# ProbadorDeCables_Conexiones_A.net
KiCad netlist of a schematic drawn in Altium Designer
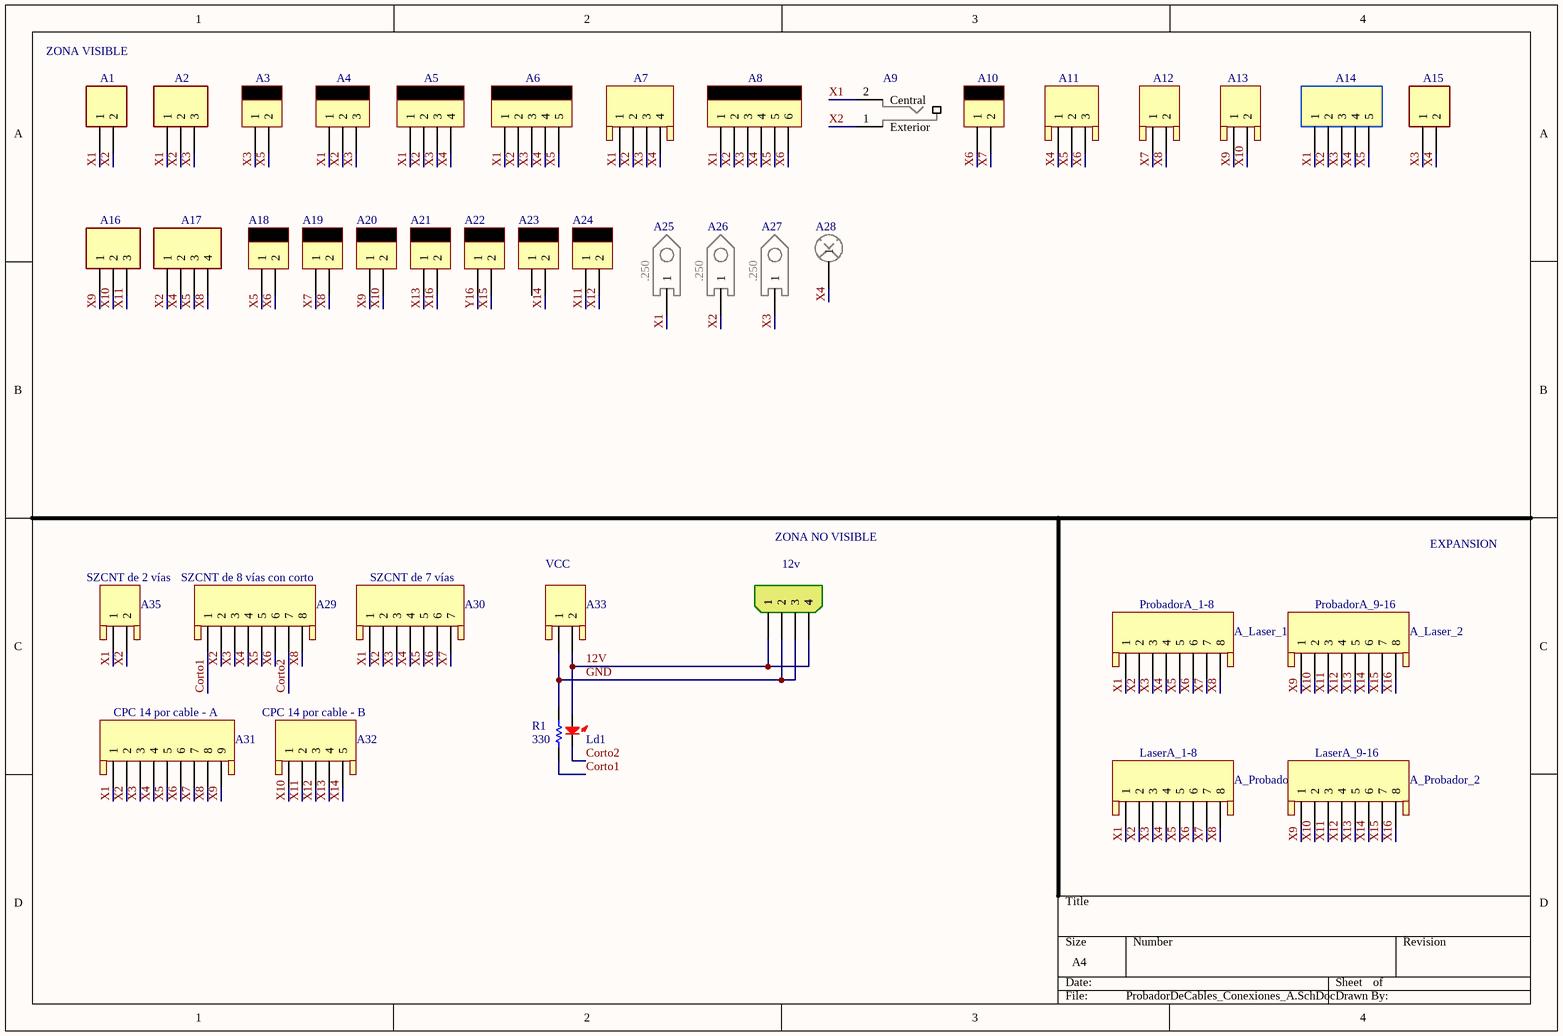
[diagram p0: ProbadorDeCables_Conexiones_A.SchDoc]

(export (version "E")
  (design (tool "Eeschema 10.0.6"))
  (components
    (comp (ref "12v")
      (value "MAZ 103 y 104")
      (footprint "794285-1")
      (description "CONN HDR 4POS 0.2 TIN PCB")
      (libsource (lib "Nahuel_Connectors_BODY") (part "794285-1"))
    )
    (comp (ref "A1")
      (value "JST_2.5_2")
      (footprint "B2B-XH-A")
      (description "CONN HEADER XH TOP 2POS 2.5MM")
      (fields (field (name "PUBLISHER") "Altium Limited"))
      (libsource (lib "Nahuel_Connectors_BODY") (part "JST_2.5_2"))
    )
    (comp (ref "A2")
      (value "JST_2.5_3")
      (footprint "B3B-XH-A")
      (description "CONN HEADER XH TOP 3POS 2.5MM")
      (fields (field (name "PUBLISHER") "Altium Limited"))
      (libsource (lib "Nahuel_Connectors_BODY") (part "JST_2.5_3"))
    )
    (comp (ref "A3")
      (value "Para_SL-156__640445-2")
      (footprint "640445-2")
      (description "CONN HEADER VERT 2POS .156 TIN")
      (libsource (lib "Nahuel_Connectors_BODY") (part "Para_SL-156__640445-2"))
    )
    (comp (ref "A4")
      (value "Para_SL-156__640445-3")
      (footprint "640445-3")
      (description "CONN HEADER VERT 3POS .156 TIN")
      (libsource (lib "Nahuel_Connectors_BODY") (part "Para_SL-156__640445-3"))
    )
    (comp (ref "A5")
      (value "Para_SL-156__640445-4")
      (footprint "640445-4")
      (description "CONN HEADER VERT 4POS .156 TIN")
      (libsource (lib "Nahuel_Connectors_BODY") (part "Para_SL-156__640445-4"))
    )
    (comp (ref "A6")
      (value "Para_SL-156__640445-5")
      (footprint "640445-5")
      (description "CONN HEADER VERT 5POS .156 TIN")
      (libsource (lib "Nahuel_Connectors_BODY") (part "Para_SL-156__640445-5"))
    )
    (comp (ref "A7")
      (value "Para_CST_100__640456-4")
      (footprint "640456-4")
      (description "CONN HEADER VERT 4POS .100 TIN")
      (fields (field (name "PUBLISHER") "Altium Limited"))
      (libsource (lib "Nahuel_Connectors_BODY") (part "Para_CST_100__640456-4"))
    )
    (comp (ref "A8")
      (value "Para_SL-156__640445-6")
      (footprint "640445-6")
      (description "CONN HEADER VERT 6POS .156 TIN")
      (libsource (lib "Nahuel_Connectors_BODY") (part "Para_SL-156__640445-6"))
    )
    (comp (ref "A9")
      (value "RCA mono para placa - Negro")
      (footprint "RCJ-021")
      (description "CONN RCA JACK MONO 3.2MM PCB")
      (libsource (lib "Nahuel_Connectors_BODY") (part "RCA mono para placa - Negro"))
    )
    (comp (ref "A10")
      (value "Para_SL-156__640445-2")
      (footprint "640445-2")
      (description "CONN HEADER VERT 2POS .156 TIN")
      (libsource (lib "Nahuel_Connectors_BODY") (part "Para_SL-156__640445-2"))
    )
    (comp (ref "A11")
      (value "Para_CST_100__640456-3")
      (footprint "640456-3")
      (description "CONN HEADER VERT 3POS .100 TIN")
      (fields (field (name "PUBLISHER") "Altium Limited"))
      (libsource (lib "Nahuel_Connectors_BODY") (part "Para_CST_100__640456-3"))
    )
    (comp (ref "A12")
      (value "Para_CST_100__640456-2")
      (footprint "640456-2")
      (description "CONN HEADER VERT 2POS .100 TIN")
      (fields (field (name "PUBLISHER") "Altium Limited"))
      (libsource (lib "Nahuel_Connectors_BODY") (part "Para_CST_100__640456-2"))
    )
    (comp (ref "A13")
      (value "Para_CST_100__640456-2")
      (footprint "640456-2")
      (description "CONN HEADER VERT 2POS .100 TIN")
      (fields (field (name "PUBLISHER") "Altium Limited"))
      (libsource (lib "Nahuel_Connectors_BODY") (part "Para_CST_100__640456-2"))
    )
    (comp (ref "A14")
      (value "USB 2_0 micro B")
      (footprint "USB2.0_MicroB")
      (description "CONN RCPT USB2.0 MICRO B SMD R/A")
      (libsource (lib "Nahuel_Connectors_BODY") (part "USB 2_0 micro B"))
    )
    (comp (ref "A15")
      (value "JST_2.5_2")
      (footprint "B2B-XH-A")
      (description "CONN HEADER XH TOP 2POS 2.5MM")
      (fields (field (name "PUBLISHER") "Altium Limited"))
      (libsource (lib "Nahuel_Connectors_BODY") (part "JST_2.5_2"))
    )
    (comp (ref "A16")
      (value "JST_2.5_3")
      (footprint "B3B-XH-A")
      (description "CONN HEADER XH TOP 3POS 2.5MM")
      (fields (field (name "PUBLISHER") "Altium Limited"))
      (libsource (lib "Nahuel_Connectors_BODY") (part "JST_2.5_3"))
    )
    (comp (ref "A17")
      (value "JST_2.5_4")
      (footprint "B4B-XH-A")
      (description "CONN HEADER XH TOP 4POS 2.5MM")
      (fields (field (name "PUBLISHER") "Altium Limited"))
      (libsource (lib "Nahuel_Connectors_BODY") (part "JST_2.5_4"))
    )
    (comp (ref "A18")
      (value "Para_SL-156__640445-2")
      (footprint "640445-2")
      (description "CONN HEADER VERT 2POS .156 TIN")
      (libsource (lib "Nahuel_Connectors_BODY") (part "Para_SL-156__640445-2"))
    )
    (comp (ref "A19")
      (value "Para_SL-156__640445-2")
      (footprint "640445-2")
      (description "CONN HEADER VERT 2POS .156 TIN")
      (libsource (lib "Nahuel_Connectors_BODY") (part "Para_SL-156__640445-2"))
    )
    (comp (ref "A20")
      (value "Para_SL-156__640445-2")
      (footprint "640445-2")
      (description "CONN HEADER VERT 2POS .156 TIN")
      (libsource (lib "Nahuel_Connectors_BODY") (part "Para_SL-156__640445-2"))
    )
    (comp (ref "A21")
      (value "Para_SL-156__640445-2")
      (footprint "640445-2")
      (description "CONN HEADER VERT 2POS .156 TIN")
      (libsource (lib "Nahuel_Connectors_BODY") (part "Para_SL-156__640445-2"))
    )
    (comp (ref "A22")
      (value "Para_SL-156__640445-2")
      (footprint "640445-2")
      (description "CONN HEADER VERT 2POS .156 TIN")
      (libsource (lib "Nahuel_Connectors_BODY") (part "Para_SL-156__640445-2"))
    )
    (comp (ref "A23")
      (value "Para_SL-156__640445-2")
      (footprint "640445-2")
      (description "CONN HEADER VERT 2POS .156 TIN")
      (libsource (lib "Nahuel_Connectors_BODY") (part "Para_SL-156__640445-2"))
    )
    (comp (ref "A24")
      (value "Para_SL-156__640445-2")
      (footprint "640445-2")
      (description "CONN HEADER VERT 2POS .156 TIN")
      (libsource (lib "Nahuel_Connectors_BODY") (part "Para_SL-156__640445-2"))
    )
    (comp (ref "A25")
      (value "Pala macho 6.3 para placa")
      (footprint "Nahuel_Connectors_BODY:Pala macho 6.3 para placa")
      (description "CONN QC TAB 0.250 SOLDER")
      (libsource (lib "Nahuel_Connectors_BODY") (part "Pala macho 6.3 para placa"))
    )
    (comp (ref "A26")
      (value "Pala macho 6.3 para placa")
      (footprint "Nahuel_Connectors_BODY:Pala macho 6.3 para placa")
      (description "CONN QC TAB 0.250 SOLDER")
      (libsource (lib "Nahuel_Connectors_BODY") (part "Pala macho 6.3 para placa"))
    )
    (comp (ref "A27")
      (value "Pala macho 6.3 para placa")
      (footprint "Nahuel_Connectors_BODY:Pala macho 6.3 para placa")
      (description "CONN QC TAB 0.250 SOLDER")
      (libsource (lib "Nahuel_Connectors_BODY") (part "Pala macho 6.3 para placa"))
    )
    (comp (ref "A28")
      (value "SCREW M4 4 PIN PCB")
      (footprint "SCREW M4 4 PIN PCB")
      (description "TERM SCREW M4 4 PIN PCB")
      (libsource (lib "Nahuel_Connectors_BODY") (part "SCREW M4 4 PIN PCB"))
    )
    (comp (ref "A29")
      (value "SZCNT de 8 vías con corto")
      (footprint "640456-8")
      (description "CONN HEADER VERT 8POS .100 TIN")
      (fields (field (name "PUBLISHER") "Altium Limited"))
      (libsource (lib "Nahuel_Connectors_BODY") (part "Para_CST_100__640456-8"))
    )
    (comp (ref "A30")
      (value "SZCNT de 7 vías")
      (footprint "640456-7")
      (description "CONN HEADER VERT 7POS .100 TIN")
      (fields (field (name "PUBLISHER") "Altium Limited"))
      (libsource (lib "Nahuel_Connectors_BODY") (part "Para_CST_100__640456-7"))
    )
    (comp (ref "A31")
      (value "CPC 14 por cable - A")
      (footprint "640456-9")
      (description "CONN HEADER VERT 9POS .100 TIN")
      (fields (field (name "PUBLISHER") "Altium Limited"))
      (libsource (lib "Nahuel_Connectors_BODY") (part "Para_CST_100__640456-9"))
    )
    (comp (ref "A32")
      (value "CPC 14 por cable - B")
      (footprint "640456-5")
      (description "CONN HEADER VERT 5POS .100 TIN")
      (fields (field (name "PUBLISHER") "Altium Limited"))
      (libsource (lib "Nahuel_Connectors_BODY") (part "Para_CST_100__640456-5"))
    )
    (comp (ref "A33")
      (value "VCC")
      (footprint "640456-2")
      (description "CONN HEADER VERT 2POS .100 TIN")
      (fields (field (name "PUBLISHER") "Altium Limited"))
      (libsource (lib "Nahuel_Connectors_BODY") (part "Para_CST_100__640456-2"))
    )
    (comp (ref "A35")
      (value "SZCNT de 2 vías")
      (footprint "640456-2")
      (description "CONN HEADER VERT 2POS .100 TIN")
      (fields (field (name "PUBLISHER") "Altium Limited"))
      (libsource (lib "Nahuel_Connectors_BODY") (part "Para_CST_100__640456-2"))
    )
    (comp (ref "A_Laser_1")
      (value "ProbadorA_1-8")
      (footprint "640456-8")
      (description "CONN HEADER VERT 8POS .100 TIN")
      (libsource (lib "Nahuel_Connectors_BODY") (part "Para_CST_100__640456-8"))
    )
    (comp (ref "A_Laser_2")
      (value "ProbadorA_9-16")
      (footprint "640456-8")
      (description "CONN HEADER VERT 8POS .100 TIN")
      (libsource (lib "Nahuel_Connectors_BODY") (part "Para_CST_100__640456-8"))
    )
    (comp (ref "A_Probador_1")
      (value "LaserA_1-8")
      (footprint "640456-8")
      (description "CONN HEADER VERT 8POS .100 TIN")
      (libsource (lib "Nahuel_Connectors_BODY") (part "Para_CST_100__640456-8"))
    )
    (comp (ref "A_Probador_2")
      (value "LaserA_9-16")
      (footprint "640456-8")
      (description "CONN HEADER VERT 8POS .100 TIN")
      (libsource (lib "Nahuel_Connectors_BODY") (part "Para_CST_100__640456-8"))
    )
    (comp (ref "Ld1")
      (value "PinesParaLed")
      (footprint "Nahuel_TH_BODY:Jumper-Simple")
      (description "CONN HEADER 2 POS 2.54")
      (fields (field (name "PUBLISHER") "Altium Limited"))
      (libsource (lib "Nahuel_Connectors_BODY") (part "PinesParaLed"))
    )
    (comp (ref "R1")
      (value "330")
      (footprint "Nahuel_SMD_Body:R_0805")
      (description "RES SMD 330 OHM 1% 1/8W 0805")
      (fields (field (name "PUBLISHER") "Altium Limited"))
      (libsource (lib "Nahuel_SMD_Body") (part "R_330_0805"))
    )
  )
  (nets
    (net (code "1") (name "/12V") (class "Default")
      (node (ref "12v") (pin "1") (pinfunction "1_1") (pintype "passive"))
      (node (ref "12v") (pin "4") (pinfunction "4_4") (pintype "passive"))
      (node (ref "A33") (pin "2") (pinfunction "2_2") (pintype "passive"))
      (node (ref "Ld1") (pin "1") (pinfunction "1_1") (pintype "passive"))
    )
    (net (code "2") (name "/Corto1") (class "Default")
      (node (ref "A29") (pin "1") (pinfunction "1_1") (pintype "passive"))
      (node (ref "R1") (pin "1") (pinfunction "1_1") (pintype "passive"))
    )
    (net (code "3") (name "/Corto2") (class "Default")
      (node (ref "A29") (pin "7") (pinfunction "7_7") (pintype "passive"))
      (node (ref "Ld1") (pin "2") (pinfunction "2_2") (pintype "passive"))
    )
    (net (code "4") (name "/GND") (class "Default")
      (node (ref "12v") (pin "2") (pinfunction "2_2") (pintype "passive"))
      (node (ref "12v") (pin "3") (pinfunction "3_3") (pintype "passive"))
      (node (ref "A33") (pin "1") (pinfunction "1_1") (pintype "passive"))
      (node (ref "R1") (pin "2") (pinfunction "2_2") (pintype "passive"))
    )
    (net (code "5") (name "/X1") (class "Default")
      (node (ref "A1") (pin "1") (pinfunction "1_1") (pintype "passive"))
      (node (ref "A14") (pin "1") (pinfunction "1_1") (pintype "passive"))
      (node (ref "A2") (pin "1") (pinfunction "1_1") (pintype "passive"))
      (node (ref "A25") (pin "1") (pinfunction "1_1") (pintype "passive"))
      (node (ref "A30") (pin "1") (pinfunction "1_1") (pintype "passive"))
      (node (ref "A31") (pin "1") (pinfunction "1_1") (pintype "passive"))
      (node (ref "A35") (pin "1") (pinfunction "1_1") (pintype "passive"))
      (node (ref "A4") (pin "1") (pinfunction "1_1") (pintype "passive"))
      (node (ref "A5") (pin "1") (pinfunction "1_1") (pintype "passive"))
      (node (ref "A6") (pin "1") (pinfunction "1_1") (pintype "passive"))
      (node (ref "A7") (pin "1") (pinfunction "1_1") (pintype "passive"))
      (node (ref "A8") (pin "1") (pinfunction "1_1") (pintype "passive"))
      (node (ref "A9") (pin "2") (pinfunction "Central_2") (pintype "passive"))
      (node (ref "A_Laser_1") (pin "1") (pinfunction "1_1") (pintype "passive"))
      (node (ref "A_Probador_1") (pin "1") (pinfunction "1_1") (pintype "passive"))
    )
    (net (code "6") (name "/X2") (class "Default")
      (node (ref "A1") (pin "2") (pinfunction "2_2") (pintype "passive"))
      (node (ref "A14") (pin "2") (pinfunction "2_2") (pintype "passive"))
      (node (ref "A17") (pin "1") (pinfunction "1_1") (pintype "passive"))
      (node (ref "A2") (pin "2") (pinfunction "2_2") (pintype "passive"))
      (node (ref "A26") (pin "1") (pinfunction "1_1") (pintype "passive"))
      (node (ref "A29") (pin "2") (pinfunction "2_2") (pintype "passive"))
      (node (ref "A30") (pin "2") (pinfunction "2_2") (pintype "passive"))
      (node (ref "A31") (pin "2") (pinfunction "2_2") (pintype "passive"))
      (node (ref "A35") (pin "2") (pinfunction "2_2") (pintype "passive"))
      (node (ref "A4") (pin "2") (pinfunction "2_2") (pintype "passive"))
      (node (ref "A5") (pin "2") (pinfunction "2_2") (pintype "passive"))
      (node (ref "A6") (pin "2") (pinfunction "2_2") (pintype "passive"))
      (node (ref "A7") (pin "2") (pinfunction "2_2") (pintype "passive"))
      (node (ref "A8") (pin "2") (pinfunction "2_2") (pintype "passive"))
      (node (ref "A9") (pin "1") (pinfunction "Exterior_1") (pintype "passive"))
      (node (ref "A_Laser_1") (pin "2") (pinfunction "2_2") (pintype "passive"))
      (node (ref "A_Probador_1") (pin "2") (pinfunction "2_2") (pintype "passive"))
    )
    (net (code "7") (name "/X3") (class "Default")
      (node (ref "A14") (pin "3") (pinfunction "3_3") (pintype "passive"))
      (node (ref "A15") (pin "1") (pinfunction "1_1") (pintype "passive"))
      (node (ref "A2") (pin "3") (pinfunction "3_3") (pintype "passive"))
      (node (ref "A27") (pin "1") (pinfunction "1_1") (pintype "passive"))
      (node (ref "A29") (pin "3") (pinfunction "3_3") (pintype "passive"))
      (node (ref "A3") (pin "1") (pinfunction "1_1") (pintype "passive"))
      (node (ref "A30") (pin "3") (pinfunction "3_3") (pintype "passive"))
      (node (ref "A31") (pin "3") (pinfunction "3_3") (pintype "passive"))
      (node (ref "A4") (pin "3") (pinfunction "3_3") (pintype "passive"))
      (node (ref "A5") (pin "3") (pinfunction "3_3") (pintype "passive"))
      (node (ref "A6") (pin "3") (pinfunction "3_3") (pintype "passive"))
      (node (ref "A7") (pin "3") (pinfunction "3_3") (pintype "passive"))
      (node (ref "A8") (pin "3") (pinfunction "3_3") (pintype "passive"))
      (node (ref "A_Laser_1") (pin "3") (pinfunction "3_3") (pintype "passive"))
      (node (ref "A_Probador_1") (pin "3") (pinfunction "3_3") (pintype "passive"))
    )
    (net (code "8") (name "/X4") (class "Default")
      (node (ref "A11") (pin "1") (pinfunction "1_1") (pintype "passive"))
      (node (ref "A14") (pin "4") (pinfunction "4_4") (pintype "passive"))
      (node (ref "A15") (pin "2") (pinfunction "2_2") (pintype "passive"))
      (node (ref "A17") (pin "2") (pinfunction "2_2") (pintype "passive"))
      (node (ref "A28") (pin "1") (pinfunction "1_1") (pintype "passive"))
      (node (ref "A29") (pin "4") (pinfunction "4_4") (pintype "passive"))
      (node (ref "A30") (pin "4") (pinfunction "4_4") (pintype "passive"))
      (node (ref "A31") (pin "4") (pinfunction "4_4") (pintype "passive"))
      (node (ref "A5") (pin "4") (pinfunction "4_4") (pintype "passive"))
      (node (ref "A6") (pin "4") (pinfunction "4_4") (pintype "passive"))
      (node (ref "A7") (pin "4") (pinfunction "4_4") (pintype "passive"))
      (node (ref "A8") (pin "4") (pinfunction "4_4") (pintype "passive"))
      (node (ref "A_Laser_1") (pin "4") (pinfunction "4_4") (pintype "passive"))
      (node (ref "A_Probador_1") (pin "4") (pinfunction "4_4") (pintype "passive"))
    )
    (net (code "9") (name "/X5") (class "Default")
      (node (ref "A11") (pin "2") (pinfunction "2_2") (pintype "passive"))
      (node (ref "A14") (pin "5") (pinfunction "5_5") (pintype "passive"))
      (node (ref "A17") (pin "3") (pinfunction "3_3") (pintype "passive"))
      (node (ref "A18") (pin "1") (pinfunction "1_1") (pintype "passive"))
      (node (ref "A29") (pin "5") (pinfunction "5_5") (pintype "passive"))
      (node (ref "A3") (pin "2") (pinfunction "2_2") (pintype "passive"))
      (node (ref "A30") (pin "5") (pinfunction "5_5") (pintype "passive"))
      (node (ref "A31") (pin "5") (pinfunction "5_5") (pintype "passive"))
      (node (ref "A6") (pin "5") (pinfunction "5_5") (pintype "passive"))
      (node (ref "A8") (pin "5") (pinfunction "5_5") (pintype "passive"))
      (node (ref "A_Laser_1") (pin "5") (pinfunction "5_5") (pintype "passive"))
      (node (ref "A_Probador_1") (pin "5") (pinfunction "5_5") (pintype "passive"))
    )
    (net (code "10") (name "/X6") (class "Default")
      (node (ref "A10") (pin "1") (pinfunction "1_1") (pintype "passive"))
      (node (ref "A11") (pin "3") (pinfunction "3_3") (pintype "passive"))
      (node (ref "A18") (pin "2") (pinfunction "2_2") (pintype "passive"))
      (node (ref "A29") (pin "6") (pinfunction "6_6") (pintype "passive"))
      (node (ref "A30") (pin "6") (pinfunction "6_6") (pintype "passive"))
      (node (ref "A31") (pin "6") (pinfunction "6_6") (pintype "passive"))
      (node (ref "A8") (pin "6") (pinfunction "6_6") (pintype "passive"))
      (node (ref "A_Laser_1") (pin "6") (pinfunction "6_6") (pintype "passive"))
      (node (ref "A_Probador_1") (pin "6") (pinfunction "6_6") (pintype "passive"))
    )
    (net (code "11") (name "/X7") (class "Default")
      (node (ref "A10") (pin "2") (pinfunction "2_2") (pintype "passive"))
      (node (ref "A12") (pin "1") (pinfunction "1_1") (pintype "passive"))
      (node (ref "A19") (pin "1") (pinfunction "1_1") (pintype "passive"))
      (node (ref "A30") (pin "7") (pinfunction "7_7") (pintype "passive"))
      (node (ref "A31") (pin "7") (pinfunction "7_7") (pintype "passive"))
      (node (ref "A_Laser_1") (pin "7") (pinfunction "7_7") (pintype "passive"))
      (node (ref "A_Probador_1") (pin "7") (pinfunction "7_7") (pintype "passive"))
    )
    (net (code "12") (name "/X8") (class "Default")
      (node (ref "A12") (pin "2") (pinfunction "2_2") (pintype "passive"))
      (node (ref "A17") (pin "4") (pinfunction "4_4") (pintype "passive"))
      (node (ref "A19") (pin "2") (pinfunction "2_2") (pintype "passive"))
      (node (ref "A29") (pin "8") (pinfunction "8_8") (pintype "passive"))
      (node (ref "A31") (pin "8") (pinfunction "8_8") (pintype "passive"))
      (node (ref "A_Laser_1") (pin "8") (pinfunction "8_8") (pintype "passive"))
      (node (ref "A_Probador_1") (pin "8") (pinfunction "8_8") (pintype "passive"))
    )
    (net (code "13") (name "/X9") (class "Default")
      (node (ref "A13") (pin "1") (pinfunction "1_1") (pintype "passive"))
      (node (ref "A16") (pin "1") (pinfunction "1_1") (pintype "passive"))
      (node (ref "A20") (pin "1") (pinfunction "1_1") (pintype "passive"))
      (node (ref "A31") (pin "9") (pinfunction "9_9") (pintype "passive"))
      (node (ref "A_Laser_2") (pin "1") (pinfunction "1_1") (pintype "passive"))
      (node (ref "A_Probador_2") (pin "1") (pinfunction "1_1") (pintype "passive"))
    )
    (net (code "14") (name "/X10") (class "Default")
      (node (ref "A13") (pin "2") (pinfunction "2_2") (pintype "passive"))
      (node (ref "A16") (pin "2") (pinfunction "2_2") (pintype "passive"))
      (node (ref "A20") (pin "2") (pinfunction "2_2") (pintype "passive"))
      (node (ref "A32") (pin "1") (pinfunction "1_1") (pintype "passive"))
      (node (ref "A_Laser_2") (pin "2") (pinfunction "2_2") (pintype "passive"))
      (node (ref "A_Probador_2") (pin "2") (pinfunction "2_2") (pintype "passive"))
    )
    (net (code "15") (name "/X11") (class "Default")
      (node (ref "A16") (pin "3") (pinfunction "3_3") (pintype "passive"))
      (node (ref "A24") (pin "1") (pinfunction "1_1") (pintype "passive"))
      (node (ref "A32") (pin "2") (pinfunction "2_2") (pintype "passive"))
      (node (ref "A_Laser_2") (pin "3") (pinfunction "3_3") (pintype "passive"))
      (node (ref "A_Probador_2") (pin "3") (pinfunction "3_3") (pintype "passive"))
    )
    (net (code "16") (name "/X12") (class "Default")
      (node (ref "A24") (pin "2") (pinfunction "2_2") (pintype "passive"))
      (node (ref "A32") (pin "3") (pinfunction "3_3") (pintype "passive"))
      (node (ref "A_Laser_2") (pin "4") (pinfunction "4_4") (pintype "passive"))
      (node (ref "A_Probador_2") (pin "4") (pinfunction "4_4") (pintype "passive"))
    )
    (net (code "17") (name "/X13") (class "Default")
      (node (ref "A21") (pin "1") (pinfunction "1_1") (pintype "passive"))
      (node (ref "A32") (pin "4") (pinfunction "4_4") (pintype "passive"))
      (node (ref "A_Laser_2") (pin "5") (pinfunction "5_5") (pintype "passive"))
      (node (ref "A_Probador_2") (pin "5") (pinfunction "5_5") (pintype "passive"))
    )
    (net (code "18") (name "/X14") (class "Default")
      (node (ref "A23") (pin "2") (pinfunction "2_2") (pintype "passive"))
      (node (ref "A32") (pin "5") (pinfunction "5_5") (pintype "passive"))
      (node (ref "A_Laser_2") (pin "6") (pinfunction "6_6") (pintype "passive"))
      (node (ref "A_Probador_2") (pin "6") (pinfunction "6_6") (pintype "passive"))
    )
    (net (code "19") (name "/X15") (class "Default")
      (node (ref "A22") (pin "2") (pinfunction "2_2") (pintype "passive"))
      (node (ref "A_Laser_2") (pin "7") (pinfunction "7_7") (pintype "passive"))
      (node (ref "A_Probador_2") (pin "7") (pinfunction "7_7") (pintype "passive"))
    )
    (net (code "20") (name "/X16") (class "Default")
      (node (ref "A21") (pin "2") (pinfunction "2_2") (pintype "passive"))
      (node (ref "A_Laser_2") (pin "8") (pinfunction "8_8") (pintype "passive"))
      (node (ref "A_Probador_2") (pin "8") (pinfunction "8_8") (pintype "passive"))
    )
    (net (code "21") (name "/Y16") (class "Default")
      (node (ref "A22") (pin "1") (pinfunction "1_1") (pintype "passive"))
    )
    (net (code "22") (name "unconnected-(A23-Pad1)") (class "Default")
      (node (ref "A23") (pin "1") (pinfunction "1_1") (pintype "passive"))
    )
  )
)
